# The_Flying_Jalapeno_DUMMY_v01.net
KiCad netlist of a schematic drawn in EAGLE
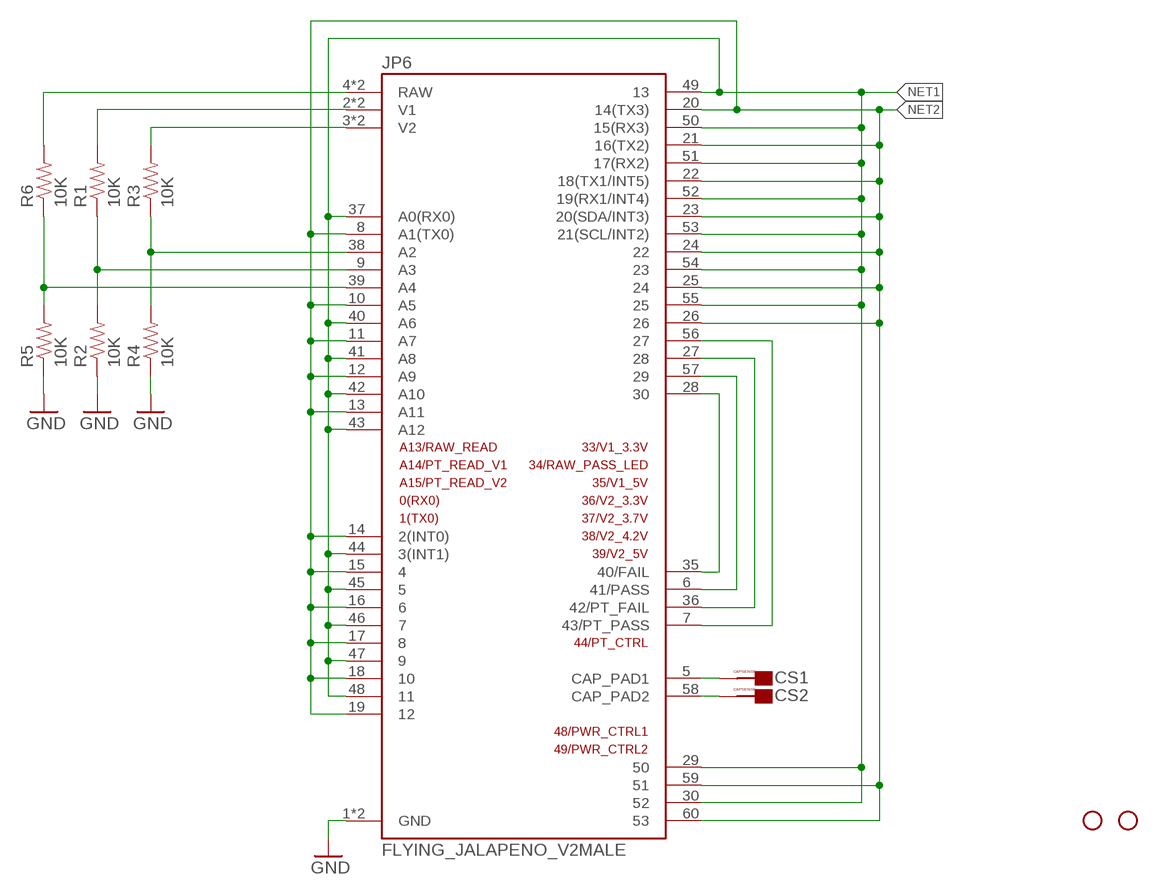
[diagram p0: schematic, sheet 1]
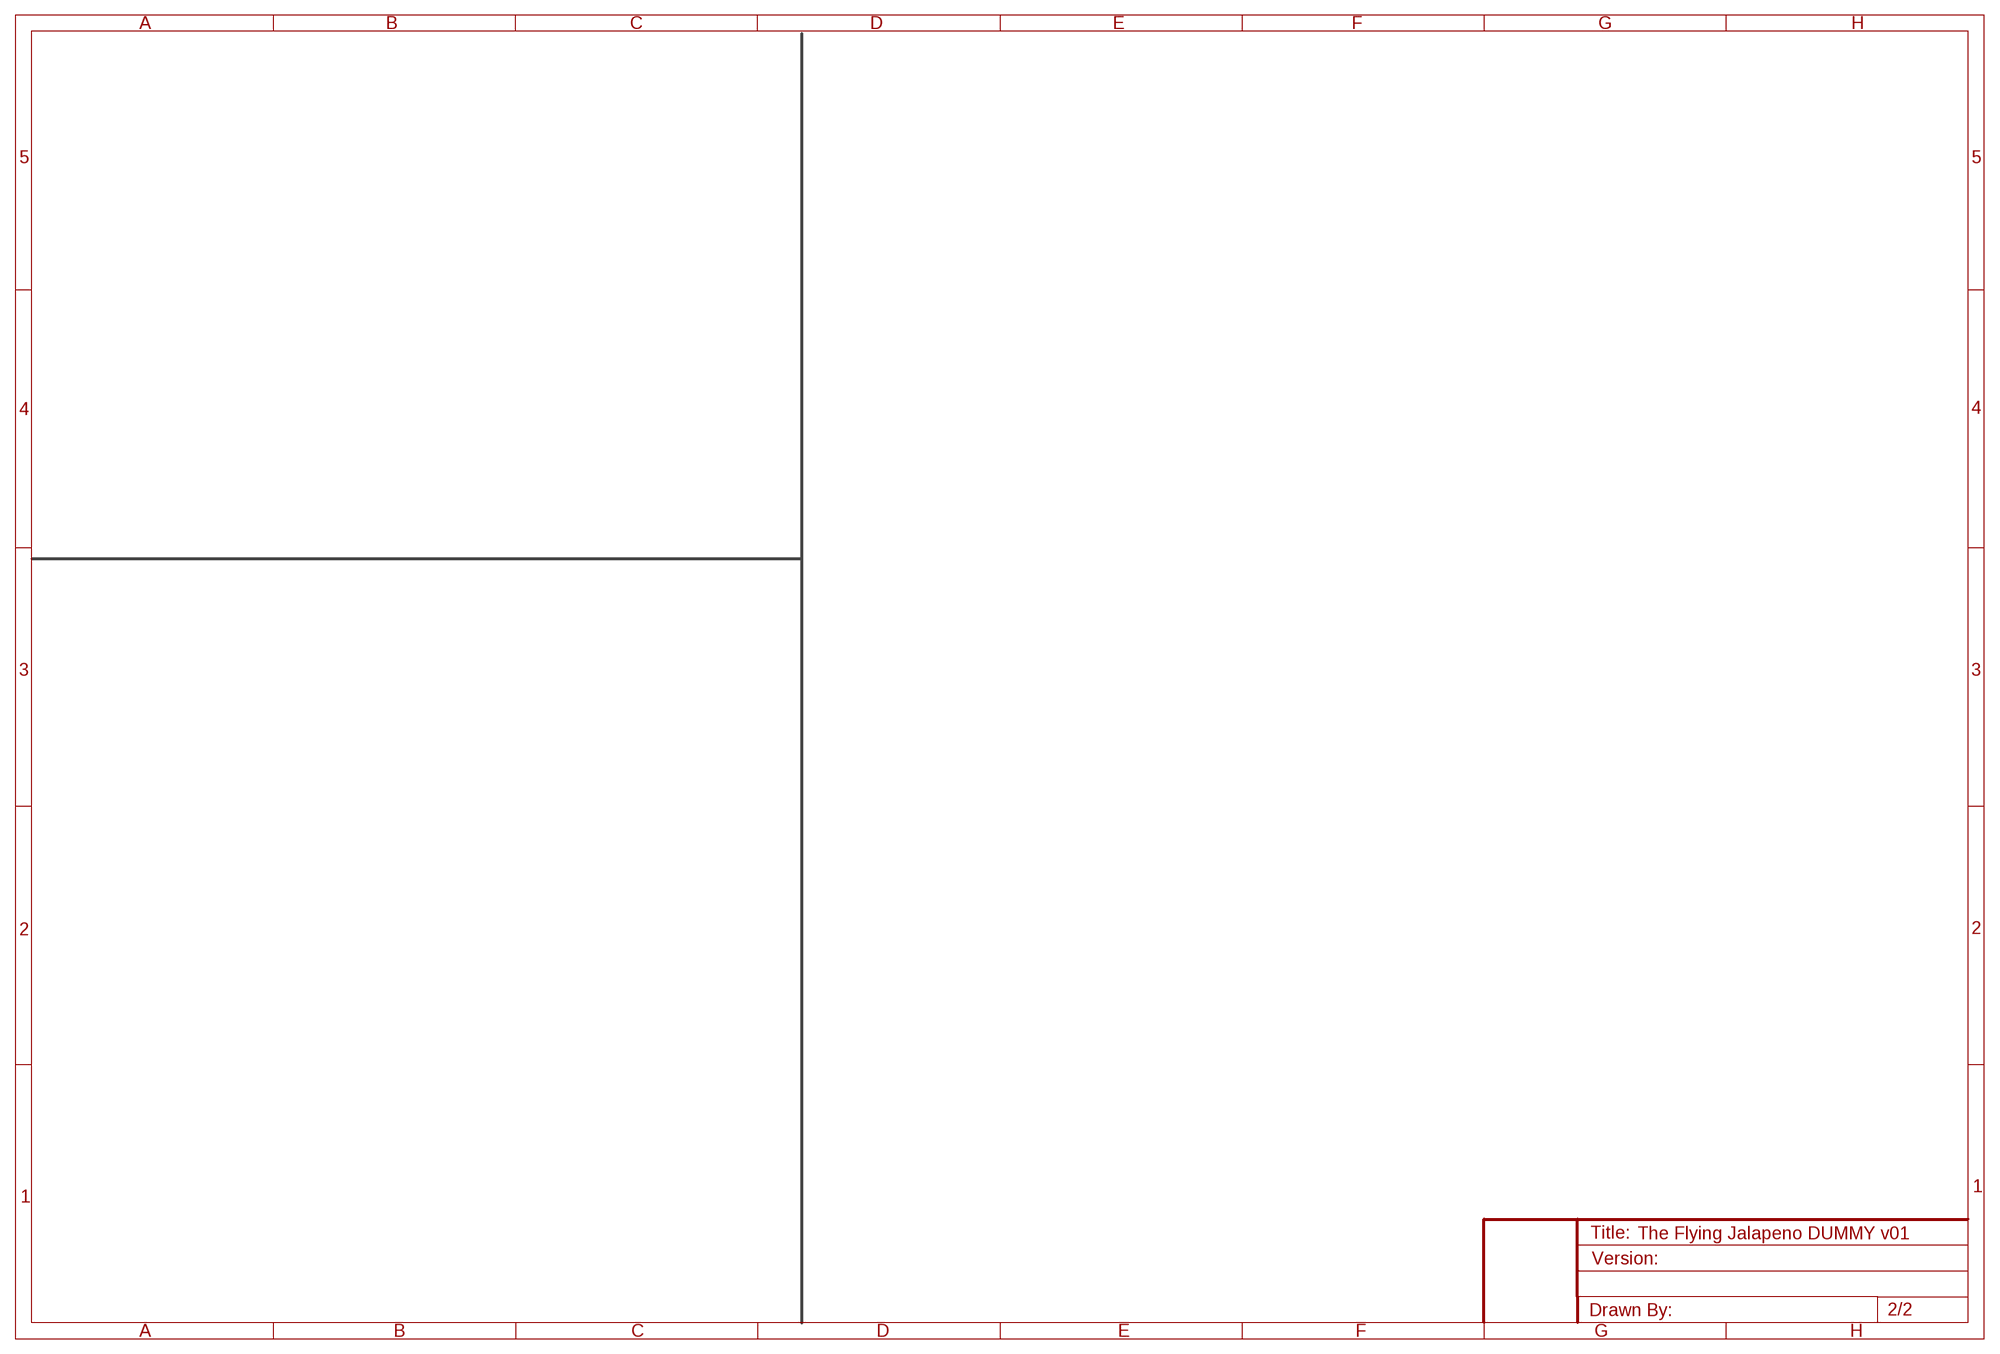
[diagram p1: schematic, sheet 2]

(export (version "E")
  (design (tool "Eeschema 10.0.6"))
  (components
    (comp (ref "CS1")
      (value "CAPSENSE_BUTTON_PAD_ONLY")
      (footprint "eagle-import:CAPSENSE_BUTTON_PADS_ONLY")
      (libsource (lib "eagle-import") (part "CAPSENSE_BUTTON_PAD_ONLY"))
    )
    (comp (ref "CS2")
      (value "CAPSENSE_BUTTON_PAD_ONLY")
      (footprint "eagle-import:CAPSENSE_BUTTON_PADS_ONLY")
      (libsource (lib "eagle-import") (part "CAPSENSE_BUTTON_PAD_ONLY"))
    )
    (comp (ref "JP6")
      (value "FLYING_JALAPENO_V2MALE")
      (footprint "eagle-import:FLYING_JALAPENO_V2_M")
      (libsource (lib "eagle-import") (part "FLYING_JALAPENO_V2MALE"))
    )
    (comp (ref "R1")
      (value "10K")
      (footprint "eagle-import:0603-RES")
      (libsource (lib "eagle-import") (part "10KOHM-1/10W-1%(0603)0603"))
    )
    (comp (ref "R2")
      (value "10K")
      (footprint "eagle-import:0603-RES")
      (libsource (lib "eagle-import") (part "10KOHM-1/10W-1%(0603)0603"))
    )
    (comp (ref "R3")
      (value "10K")
      (footprint "eagle-import:0603-RES")
      (libsource (lib "eagle-import") (part "10KOHM-1/10W-1%(0603)0603"))
    )
    (comp (ref "R4")
      (value "10K")
      (footprint "eagle-import:0603-RES")
      (libsource (lib "eagle-import") (part "10KOHM-1/10W-1%(0603)0603"))
    )
    (comp (ref "R5")
      (value "10K")
      (footprint "eagle-import:0603-RES")
      (libsource (lib "eagle-import") (part "10KOHM-1/10W-1%(0603)0603"))
    )
    (comp (ref "R6")
      (value "10K")
      (footprint "eagle-import:0603-RES")
      (libsource (lib "eagle-import") (part "10KOHM-1/10W-1%(0603)0603"))
    )
    (comp (ref "STANDOFF1")
      (value "STAND-OFFTIGHT")
      (footprint "eagle-import:STAND-OFF-TIGHT")
      (libsource (lib "eagle-import") (part "STAND-OFFTIGHT"))
    )
    (comp (ref "STANDOFF2")
      (value "STAND-OFFTIGHT")
      (footprint "eagle-import:STAND-OFF-TIGHT")
      (libsource (lib "eagle-import") (part "STAND-OFFTIGHT"))
    )
  )
  (nets
    (net (code "1") (name "GND") (class "Default")
      (node (ref "JP6") (pin "1") (pinfunction "GND_1") (pintype "bidirectional"))
      (node (ref "JP6") (pin "31") (pinfunction "GND_31") (pintype "bidirectional"))
      (node (ref "R2") (pin "1") (pinfunction "1_1") (pintype "passive"))
      (node (ref "R4") (pin "1") (pinfunction "1_1") (pintype "passive"))
      (node (ref "R5") (pin "1") (pinfunction "1_1") (pintype "passive"))
    )
    (net (code "2") (name "NET1") (class "Default")
      (node (ref "JP6") (pin "29") (pinfunction "50_29") (pintype "bidirectional"))
      (node (ref "JP6") (pin "30") (pinfunction "52_30") (pintype "bidirectional"))
      (node (ref "JP6") (pin "37") (pinfunction "A0(RX0)_37") (pintype "bidirectional"))
      (node (ref "JP6") (pin "40") (pinfunction "A6_40") (pintype "bidirectional"))
      (node (ref "JP6") (pin "41") (pinfunction "A8_41") (pintype "bidirectional"))
      (node (ref "JP6") (pin "42") (pinfunction "A10_42") (pintype "bidirectional"))
      (node (ref "JP6") (pin "43") (pinfunction "A12_43") (pintype "bidirectional"))
      (node (ref "JP6") (pin "44") (pinfunction "3(INT1)_44") (pintype "bidirectional"))
      (node (ref "JP6") (pin "45") (pinfunction "5_45") (pintype "bidirectional"))
      (node (ref "JP6") (pin "46") (pinfunction "7_46") (pintype "bidirectional"))
      (node (ref "JP6") (pin "47") (pinfunction "9_47") (pintype "bidirectional"))
      (node (ref "JP6") (pin "48") (pinfunction "11_48") (pintype "bidirectional"))
      (node (ref "JP6") (pin "49") (pinfunction "13_49") (pintype "bidirectional"))
      (node (ref "JP6") (pin "50") (pinfunction "15(RX3)_50") (pintype "bidirectional"))
      (node (ref "JP6") (pin "51") (pinfunction "17(RX2)_51") (pintype "bidirectional"))
      (node (ref "JP6") (pin "52") (pinfunction "19(RX1/INT4)_52") (pintype "bidirectional"))
      (node (ref "JP6") (pin "53") (pinfunction "21(SCL/INT2)_53") (pintype "bidirectional"))
      (node (ref "JP6") (pin "54") (pinfunction "23_54") (pintype "bidirectional"))
      (node (ref "JP6") (pin "55") (pinfunction "25_55") (pintype "bidirectional"))
    )
    (net (code "3") (name "NET2") (class "Default")
      (node (ref "JP6") (pin "10") (pinfunction "A5_10") (pintype "bidirectional"))
      (node (ref "JP6") (pin "11") (pinfunction "A7_11") (pintype "bidirectional"))
      (node (ref "JP6") (pin "12") (pinfunction "A9_12") (pintype "bidirectional"))
      (node (ref "JP6") (pin "13") (pinfunction "A11_13") (pintype "bidirectional"))
      (node (ref "JP6") (pin "14") (pinfunction "2(INT0)_14") (pintype "bidirectional"))
      (node (ref "JP6") (pin "15") (pinfunction "4_15") (pintype "bidirectional"))
      (node (ref "JP6") (pin "16") (pinfunction "6_16") (pintype "bidirectional"))
      (node (ref "JP6") (pin "17") (pinfunction "8_17") (pintype "bidirectional"))
      (node (ref "JP6") (pin "18") (pinfunction "10_18") (pintype "bidirectional"))
      (node (ref "JP6") (pin "19") (pinfunction "12_19") (pintype "bidirectional"))
      (node (ref "JP6") (pin "20") (pinfunction "14(TX3)_20") (pintype "bidirectional"))
      (node (ref "JP6") (pin "21") (pinfunction "16(TX2)_21") (pintype "bidirectional"))
      (node (ref "JP6") (pin "22") (pinfunction "18(TX1/INT5)_22") (pintype "bidirectional"))
      (node (ref "JP6") (pin "23") (pinfunction "20(SDA/INT3)_23") (pintype "bidirectional"))
      (node (ref "JP6") (pin "24") (pinfunction "22_24") (pintype "bidirectional"))
      (node (ref "JP6") (pin "25") (pinfunction "24_25") (pintype "bidirectional"))
      (node (ref "JP6") (pin "26") (pinfunction "26_26") (pintype "bidirectional"))
      (node (ref "JP6") (pin "59") (pinfunction "51_59") (pintype "bidirectional"))
      (node (ref "JP6") (pin "60") (pinfunction "53_60") (pintype "bidirectional"))
      (node (ref "JP6") (pin "8") (pinfunction "A1(TX0)_8") (pintype "bidirectional"))
    )
    (net (code "4") (name "Net-(CS1-CAPSENSE)") (class "Default")
      (node (ref "CS1") (pin "CAPSENSE_PAD") (pinfunction "CAPSENSE_CAPSENSE_PAD") (pintype "bidirectional"))
      (node (ref "JP6") (pin "5") (pinfunction "CAP_PAD1_5") (pintype "bidirectional"))
    )
    (net (code "5") (name "Net-(CS2-CAPSENSE)") (class "Default")
      (node (ref "CS2") (pin "CAPSENSE_PAD") (pinfunction "CAPSENSE_CAPSENSE_PAD") (pintype "bidirectional"))
      (node (ref "JP6") (pin "58") (pinfunction "CAP_PAD2_58") (pintype "bidirectional"))
    )
    (net (code "6") (name "Net-(JP6-27)") (class "Default")
      (node (ref "JP6") (pin "56") (pinfunction "27_56") (pintype "bidirectional"))
      (node (ref "JP6") (pin "7") (pinfunction "43/PT_PASS_7") (pintype "bidirectional"))
    )
    (net (code "7") (name "Net-(JP6-28)") (class "Default")
      (node (ref "JP6") (pin "27") (pinfunction "28_27") (pintype "bidirectional"))
      (node (ref "JP6") (pin "36") (pinfunction "42/PT_FAIL_36") (pintype "bidirectional"))
    )
    (net (code "8") (name "Net-(JP6-29)") (class "Default")
      (node (ref "JP6") (pin "57") (pinfunction "29_57") (pintype "bidirectional"))
      (node (ref "JP6") (pin "6") (pinfunction "41/PASS_6") (pintype "bidirectional"))
    )
    (net (code "9") (name "Net-(JP6-30)") (class "Default")
      (node (ref "JP6") (pin "28") (pinfunction "30_28") (pintype "bidirectional"))
      (node (ref "JP6") (pin "35") (pinfunction "40/FAIL_35") (pintype "bidirectional"))
    )
    (net (code "10") (name "Net-(JP6-A2)") (class "Default")
      (node (ref "JP6") (pin "38") (pinfunction "A2_38") (pintype "bidirectional"))
      (node (ref "R3") (pin "1") (pinfunction "1_1") (pintype "passive"))
      (node (ref "R4") (pin "2") (pinfunction "2_2") (pintype "passive"))
    )
    (net (code "11") (name "Net-(JP6-A3)") (class "Default")
      (node (ref "JP6") (pin "9") (pinfunction "A3_9") (pintype "bidirectional"))
      (node (ref "R1") (pin "1") (pinfunction "1_1") (pintype "passive"))
      (node (ref "R2") (pin "2") (pinfunction "2_2") (pintype "passive"))
    )
    (net (code "12") (name "Net-(JP6-A4)") (class "Default")
      (node (ref "JP6") (pin "39") (pinfunction "A4_39") (pintype "bidirectional"))
      (node (ref "R5") (pin "2") (pinfunction "2_2") (pintype "passive"))
      (node (ref "R6") (pin "1") (pinfunction "1_1") (pintype "passive"))
    )
    (net (code "13") (name "Net-(JP6-RAW-Pad34)") (class "Default")
      (node (ref "JP6") (pin "34") (pinfunction "RAW_34") (pintype "bidirectional"))
      (node (ref "JP6") (pin "4") (pinfunction "RAW_4") (pintype "bidirectional"))
      (node (ref "R6") (pin "2") (pinfunction "2_2") (pintype "passive"))
    )
    (net (code "14") (name "Net-(JP6-V1-Pad2)") (class "Default")
      (node (ref "JP6") (pin "2") (pinfunction "V1_2") (pintype "bidirectional"))
      (node (ref "JP6") (pin "32") (pinfunction "V1_32") (pintype "bidirectional"))
      (node (ref "R1") (pin "2") (pinfunction "2_2") (pintype "passive"))
    )
    (net (code "15") (name "Net-(JP6-V2-Pad3)") (class "Default")
      (node (ref "JP6") (pin "3") (pinfunction "V2_3") (pintype "bidirectional"))
      (node (ref "JP6") (pin "33") (pinfunction "V2_33") (pintype "bidirectional"))
      (node (ref "R3") (pin "2") (pinfunction "2_2") (pintype "passive"))
    )
  )
)
